# tinyfl_v3_t.net
KiCad netlist of a schematic drawn in Altium Designer
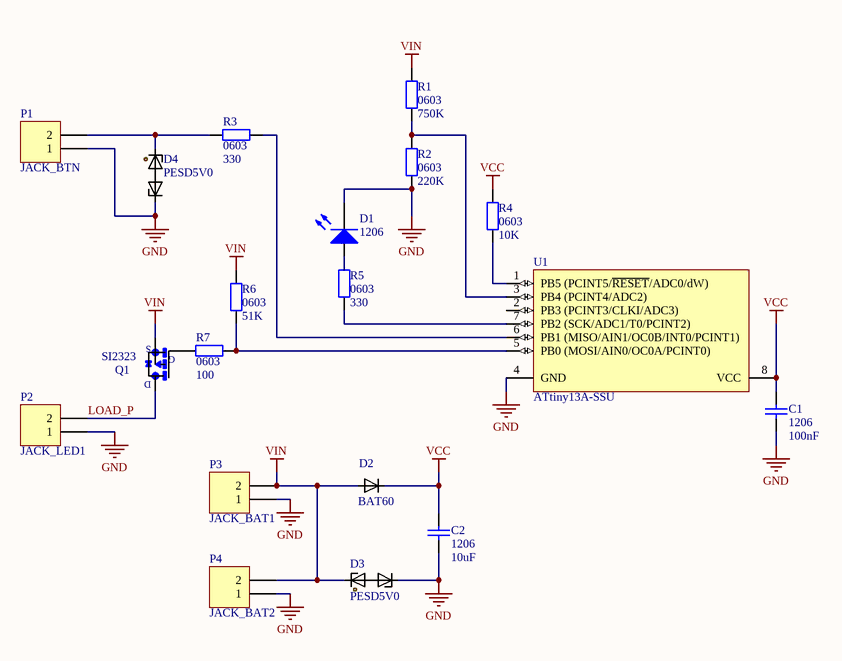
[diagram p0: tinyfl_v3_t.SchDoc]

(export (version "E")
  (design (tool "Eeschema 10.0.6"))
  (components
    (comp (ref "C1")
      (value "1206")
      (footprint "C1206")
      (description "Capacitor")
      (fields (field (name "ALTIUM_VALUE") "100nF") (field (name "PUBLISHER") "Altium Limited"))
      (libsource (lib "Miscellaneous Devices") (part "Cap"))
    )
    (comp (ref "C2")
      (value "1206")
      (footprint "C1206")
      (description "Capacitor")
      (fields (field (name "ALTIUM_VALUE") "10uF") (field (name "PUBLISHER") "Altium Limited"))
      (libsource (lib "Miscellaneous Devices") (part "Cap"))
    )
    (comp (ref "D1")
      (value "1206")
      (footprint "C1206")
      (description "Typical RED, GREEN, YELLOW, AMBER GaAs LED")
      (fields (field (name "PUBLISHER") "Altium Limited"))
      (libsource (lib "Miscellaneous Devices") (part "LED2"))
    )
    (comp (ref "D2")
      (value "BAT60")
      (footprint "*SOD323(F)")
      (description "Diode Switching 100V 0.25A 2-Pin SOD-323 T/R")
      (fields (field (name "MF") "Nexperia USA") (field (name "MP") "BAS316,135"))
      (libsource (lib "BAS316_135") (part "BAS316,135"))
    )
    (comp (ref "D3") (value "PESD5V0") (footprint "SOD-323") (libsource (lib "PESD5V0") (part "PESD5V0")))
    (comp (ref "D4") (value "PESD5V0") (footprint "SOD-323") (libsource (lib "PESD5V0") (part "PESD5V0")))
    (comp (ref "P1")
      (value "JACK_BTN")
      (footprint "HDR1X2")
      (description "Header, 2-Pin")
      (fields (field (name "PUBLISHER") "Altium Limited"))
      (libsource (lib "Miscellaneous Connectors") (part "Header 2"))
    )
    (comp (ref "P2")
      (value "JACK_LED1")
      (footprint "HDR1X2")
      (description "Header, 2-Pin")
      (fields (field (name "PUBLISHER") "Altium Limited"))
      (libsource (lib "Miscellaneous Connectors") (part "Header 2"))
    )
    (comp (ref "P3")
      (value "JACK_BAT1")
      (footprint "HDR1X2")
      (description "Header, 2-Pin")
      (fields (field (name "PUBLISHER") "Altium Limited"))
      (libsource (lib "Miscellaneous Connectors") (part "Header 2"))
    )
    (comp (ref "P4")
      (value "JACK_BAT2")
      (footprint "HDR1X2")
      (description "Header, 2-Pin")
      (fields (field (name "PUBLISHER") "Altium Limited"))
      (libsource (lib "Miscellaneous Connectors") (part "Header 2"))
    )
    (comp (ref "Q1")
      (value "SI2323")
      (footprint "SOT23")
      (description "P-CH SOT-23 Mosfet")
      (fields (field (name "MP") "AO3401"))
      (libsource (lib "AO3401") (part "AO3401"))
    )
    (comp (ref "R1")
      (value "0603")
      (footprint "1608[0603]")
      (description "Resistor")
      (fields (field (name "ALTIUM_VALUE") "750K") (field (name "PUBLISHER") "Altium Limited"))
      (libsource (lib "Miscellaneous Devices") (part "Res2"))
    )
    (comp (ref "R2")
      (value "0603")
      (footprint "1608[0603]")
      (description "Resistor")
      (fields (field (name "ALTIUM_VALUE") "220K") (field (name "PUBLISHER") "Altium Limited"))
      (libsource (lib "Miscellaneous Devices") (part "Res2"))
    )
    (comp (ref "R3")
      (value "0603")
      (footprint "1608[0603]")
      (description "Resistor")
      (fields (field (name "ALTIUM_VALUE") "330") (field (name "PUBLISHER") "Altium Limited"))
      (libsource (lib "") (part "Res2_2"))
    )
    (comp (ref "R4")
      (value "0603")
      (footprint "1608[0603]")
      (description "Resistor")
      (fields (field (name "ALTIUM_VALUE") "10K") (field (name "PUBLISHER") "Altium Limited"))
      (libsource (lib "") (part "Res2_1"))
    )
    (comp (ref "R5")
      (value "0603")
      (footprint "1608[0603]")
      (description "Resistor")
      (fields (field (name "ALTIUM_VALUE") "330") (field (name "PUBLISHER") "Altium Limited"))
      (libsource (lib "Miscellaneous Devices") (part "Res2"))
    )
    (comp (ref "R6")
      (value "0603")
      (footprint "1608[0603]")
      (description "Resistor")
      (fields (field (name "ALTIUM_VALUE") "51K") (field (name "PUBLISHER") "Altium Limited"))
      (libsource (lib "") (part "Res2_1"))
    )
    (comp (ref "R7")
      (value "0603")
      (footprint "1608[0603]")
      (description "Resistor")
      (fields (field (name "ALTIUM_VALUE") "100") (field (name "PUBLISHER") "Altium Limited"))
      (libsource (lib "") (part "Res2_2"))
    )
    (comp (ref "U1")
      (value "ATtiny13A-SSU")
      (footprint "8S1_M")
      (fields (field (name "PUBLISHER") "Altium Limited"))
      (libsource (lib "Atmel Microcontroller 8-Bit tinyAVR") (part "ATtiny13A-SSU"))
    )
  )
  (nets
    (net (code "1") (name "/LOAD_P") (class "Default")
      (node (ref "P2") (pin "2") (pinfunction "2_2") (pintype "passive"))
      (node (ref "Q1") (pin "3") (pinfunction "D_3") (pintype "passive"))
    )
    (net (code "2") (name "GND") (class "Default")
      (node (ref "C1") (pin "2") (pinfunction "2_2") (pintype "passive"))
      (node (ref "C2") (pin "2") (pinfunction "2_2") (pintype "passive"))
      (node (ref "D1") (pin "2") (pinfunction "K_2") (pintype "passive"))
      (node (ref "D3") (pin "2") (pinfunction "K_2") (pintype "passive"))
      (node (ref "D4") (pin "2") (pinfunction "K_2") (pintype "passive"))
      (node (ref "P1") (pin "1") (pinfunction "1_1") (pintype "passive"))
      (node (ref "P2") (pin "1") (pinfunction "1_1") (pintype "passive"))
      (node (ref "P3") (pin "1") (pinfunction "1_1") (pintype "passive"))
      (node (ref "P4") (pin "1") (pinfunction "1_1") (pintype "passive"))
      (node (ref "R2") (pin "2") (pinfunction "2_2") (pintype "passive"))
      (node (ref "U1") (pin "4") (pinfunction "GND_4") (pintype "power_in"))
    )
    (net (code "3") (name "Net-(D1-A)") (class "Default")
      (node (ref "D1") (pin "1") (pinfunction "A_1") (pintype "passive"))
      (node (ref "R5") (pin "1") (pinfunction "1_1") (pintype "passive"))
    )
    (net (code "4") (name "Net-(D4-A)") (class "Default")
      (node (ref "D4") (pin "1") (pinfunction "A_1") (pintype "passive"))
      (node (ref "P1") (pin "2") (pinfunction "2_2") (pintype "passive"))
      (node (ref "R3") (pin "2") (pinfunction "2_2") (pintype "passive"))
    )
    (net (code "5") (name "Net-(Q1-G)") (class "Default")
      (node (ref "Q1") (pin "1") (pinfunction "G_1") (pintype "passive"))
      (node (ref "R7") (pin "2") (pinfunction "2_2") (pintype "passive"))
    )
    (net (code "6") (name "Net-(U1-PB0_(MOSI{slash}AIN0{slash}OC0A{slash}PCINT0))") (class "Default")
      (node (ref "R6") (pin "1") (pinfunction "1_1") (pintype "passive"))
      (node (ref "R7") (pin "1") (pinfunction "1_1") (pintype "passive"))
      (node (ref "U1") (pin "5") (pinfunction "PB0_(MOSI/AIN0/OC0A/PCINT0)_5") (pintype "bidirectional"))
    )
    (net (code "7") (name "Net-(U1-PB1_(MISO{slash}AIN1{slash}OC0B{slash}INT0{slash}PCINT1))") (class "Default")
      (node (ref "R3") (pin "1") (pinfunction "1_1") (pintype "passive"))
      (node (ref "U1") (pin "6") (pinfunction "PB1_(MISO/AIN1/OC0B/INT0/PCINT1)_6") (pintype "bidirectional"))
    )
    (net (code "8") (name "Net-(U1-PB2_(SCK{slash}ADC1{slash}T0{slash}PCINT2))") (class "Default")
      (node (ref "R5") (pin "2") (pinfunction "2_2") (pintype "passive"))
      (node (ref "U1") (pin "7") (pinfunction "PB2_(SCK/ADC1/T0/PCINT2)_7") (pintype "bidirectional"))
    )
    (net (code "9") (name "Net-(U1-PB4_(PCINT4{slash}ADC2))") (class "Default")
      (node (ref "R1") (pin "2") (pinfunction "2_2") (pintype "passive"))
      (node (ref "R2") (pin "1") (pinfunction "1_1") (pintype "passive"))
      (node (ref "U1") (pin "3") (pinfunction "PB4_(PCINT4/ADC2)_3") (pintype "bidirectional"))
    )
    (net (code "10") (name "Net-(U1-PB5_(PCINT5{slash}~{RESET}{slash}ADC0{slash}dW))") (class "Default")
      (node (ref "R4") (pin "1") (pinfunction "1_1") (pintype "passive"))
      (node (ref "U1") (pin "1") (pinfunction "PB5_(PCINT5/~{RESET}/ADC0/dW)_1") (pintype "bidirectional"))
    )
    (net (code "11") (name "VCC") (class "Default")
      (node (ref "C1") (pin "1") (pinfunction "1_1") (pintype "passive"))
      (node (ref "C2") (pin "1") (pinfunction "1_1") (pintype "passive"))
      (node (ref "D2") (pin "1") (pinfunction "K_1") (pintype "passive"))
      (node (ref "R4") (pin "2") (pinfunction "2_2") (pintype "passive"))
      (node (ref "U1") (pin "8") (pinfunction "VCC_8") (pintype "power_in"))
    )
    (net (code "12") (name "VIN") (class "Default")
      (node (ref "D2") (pin "2") (pinfunction "A_2") (pintype "passive"))
      (node (ref "D3") (pin "1") (pinfunction "A_1") (pintype "passive"))
      (node (ref "P3") (pin "2") (pinfunction "2_2") (pintype "passive"))
      (node (ref "P4") (pin "2") (pinfunction "2_2") (pintype "passive"))
      (node (ref "Q1") (pin "2") (pinfunction "S_2") (pintype "passive"))
      (node (ref "R1") (pin "1") (pinfunction "1_1") (pintype "passive"))
      (node (ref "R6") (pin "2") (pinfunction "2_2") (pintype "passive"))
    )
    (net (code "13") (name "unconnected-(U1-PB3_(PCINT3{slash}CLKI{slash}ADC3)-Pad2)") (class "Default")
      (node (ref "U1") (pin "2") (pinfunction "PB3_(PCINT3/CLKI/ADC3)_2") (pintype "bidirectional"))
    )
  )
)
